# Apex4ROBOTS_UI_1_0.net
KiCad netlist of a schematic drawn in EAGLE
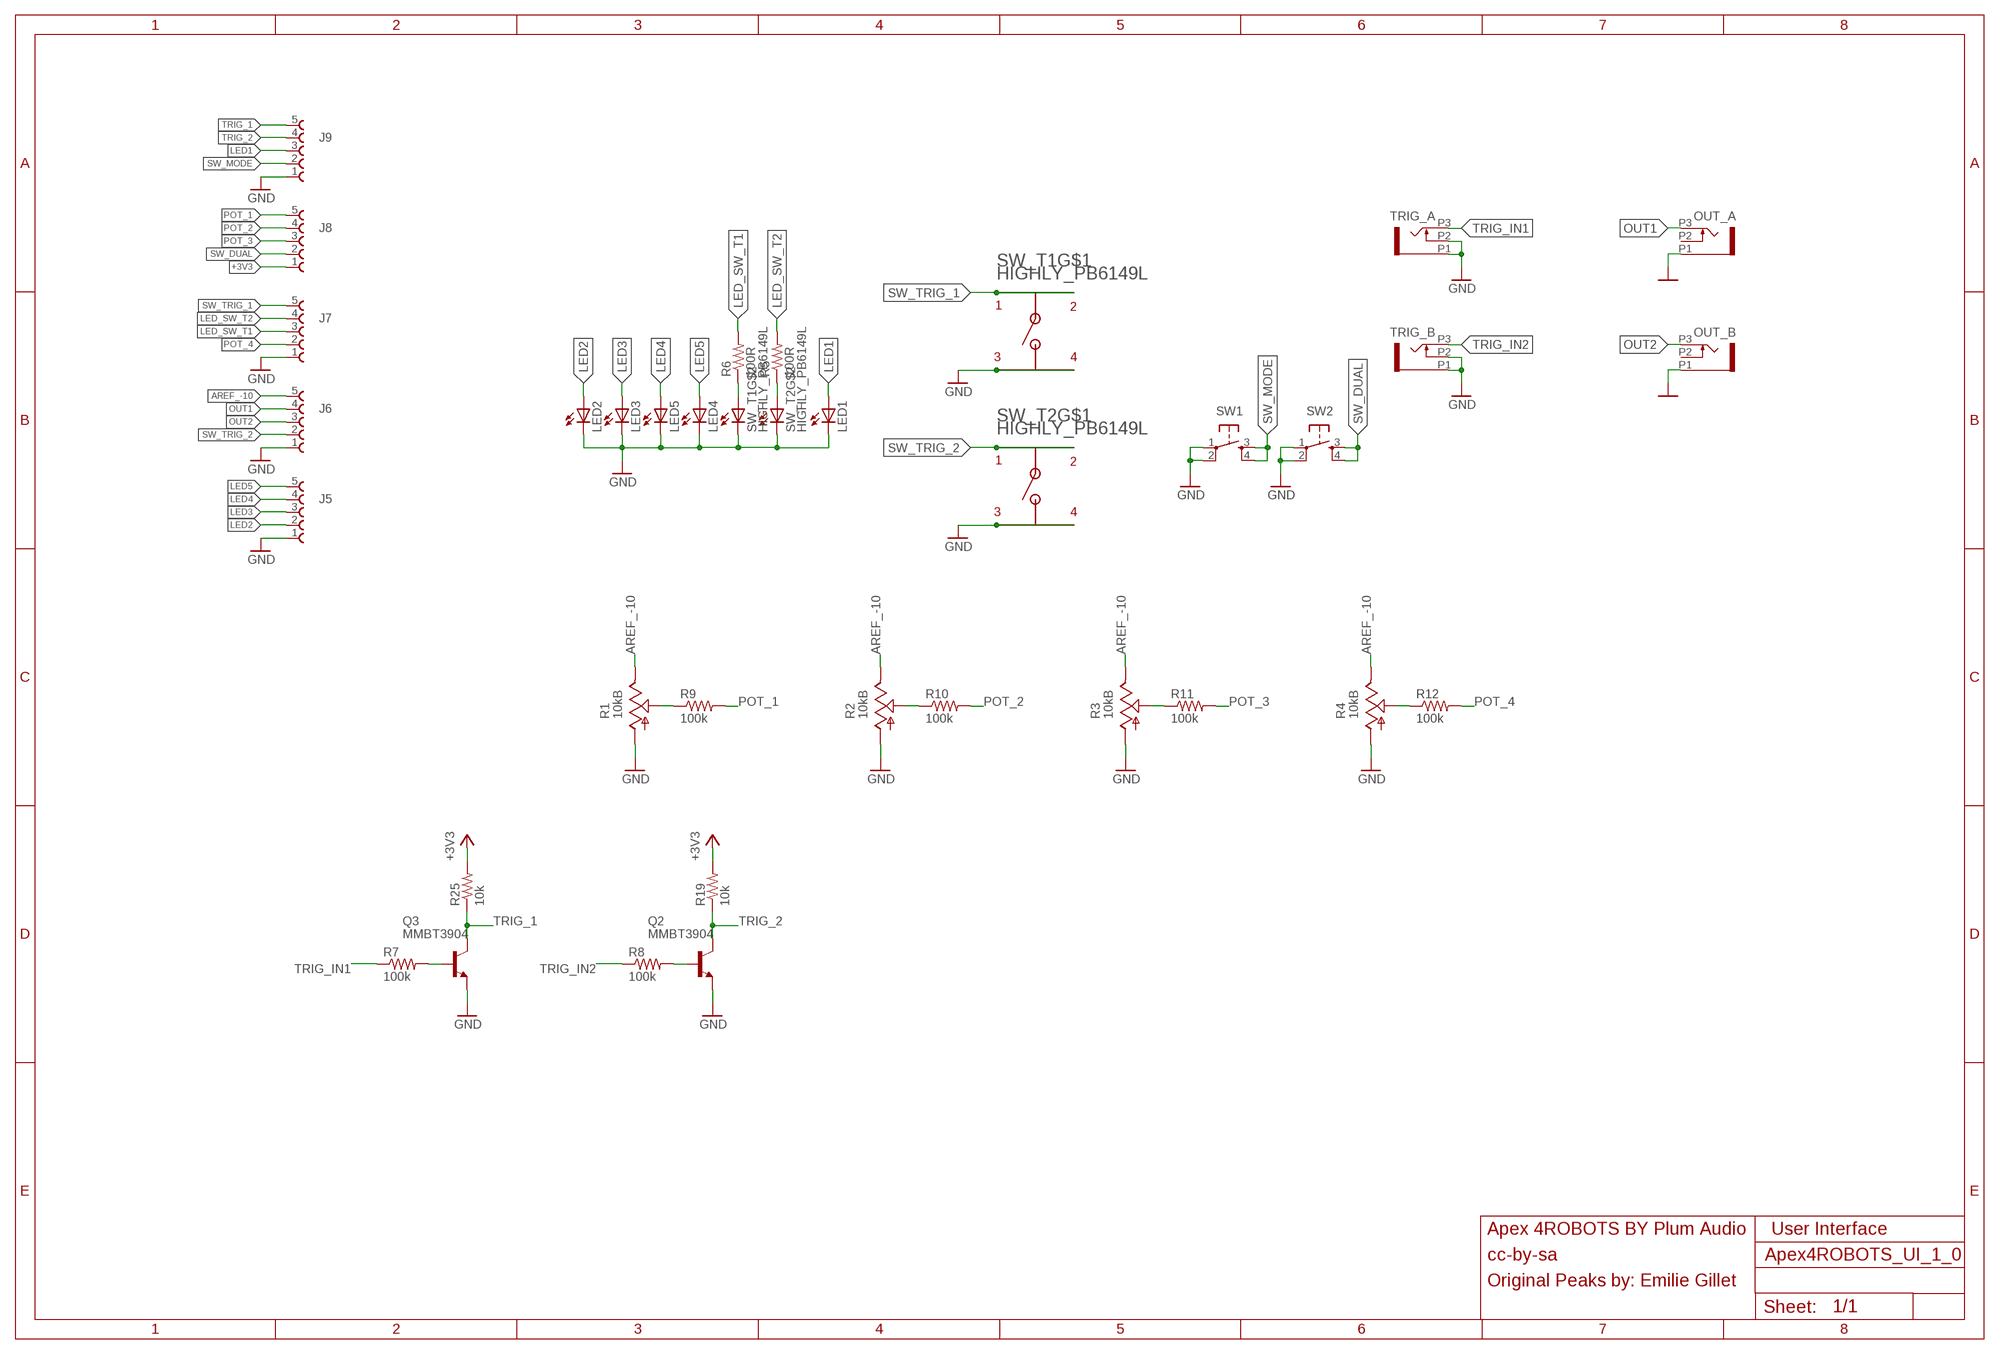
[diagram p0: schematic, sheet 1]

(export (version "E")
  (design (tool "Eeschema 10.0.6"))
  (components
    (comp (ref "J5")
      (value "61300511121")
      (footprint "eagle-import:61300511121")
      (libsource (lib "eagle-import") (part "61300511121"))
    )
    (comp (ref "J6")
      (value "61300511121")
      (footprint "eagle-import:61300511121")
      (libsource (lib "eagle-import") (part "61300511121"))
    )
    (comp (ref "J7")
      (value "61300511121")
      (footprint "eagle-import:61300511121")
      (libsource (lib "eagle-import") (part "61300511121"))
    )
    (comp (ref "J8")
      (value "61300511121")
      (footprint "eagle-import:61300511121")
      (libsource (lib "eagle-import") (part "61300511121"))
    )
    (comp (ref "J9")
      (value "61300511121")
      (footprint "eagle-import:61300511121")
      (libsource (lib "eagle-import") (part "61300511121"))
    )
    (comp (ref "LED1")
      (value "LED3MM")
      (footprint "eagle-import:LED3MM")
      (libsource (lib "eagle-import") (part "LED3MM"))
    )
    (comp (ref "LED2")
      (value "LED3MM")
      (footprint "eagle-import:LED3MM")
      (libsource (lib "eagle-import") (part "LED3MM"))
    )
    (comp (ref "LED3")
      (value "LED3MM")
      (footprint "eagle-import:LED3MM")
      (libsource (lib "eagle-import") (part "LED3MM"))
    )
    (comp (ref "LED4")
      (value "LED3MM")
      (footprint "eagle-import:LED3MM")
      (libsource (lib "eagle-import") (part "LED3MM"))
    )
    (comp (ref "LED5")
      (value "LED3MM")
      (footprint "eagle-import:LED3MM")
      (libsource (lib "eagle-import") (part "LED3MM"))
    )
    (comp (ref "OUT_A")
      (value "OG-PJ301_PJ301_THONKICONN6")
      (footprint "eagle-import:OG-PJ301_WQP_PJ_301M6")
      (libsource (lib "eagle-import") (part "OG-PJ301_PJ301_THONKICONN6"))
    )
    (comp (ref "OUT_B")
      (value "OG-PJ301_PJ301_THONKICONN6")
      (footprint "eagle-import:OG-PJ301_WQP_PJ_301M6")
      (libsource (lib "eagle-import") (part "OG-PJ301_PJ301_THONKICONN6"))
    )
    (comp (ref "Q2")
      (value "MMBT3904")
      (footprint "eagle-import:SOT23-BEC")
      (libsource (lib "eagle-import") (part "-NPN-SOT23-BECMMBT3904LT1"))
    )
    (comp (ref "Q3")
      (value "MMBT3904")
      (footprint "eagle-import:SOT23-BEC")
      (libsource (lib "eagle-import") (part "-NPN-SOT23-BECMMBT3904LT1"))
    )
    (comp (ref "R1")
      (value "10kB")
      (footprint "eagle-import:POTS_TALL_TRIMMER_POT_VERTICAL_SLOTED")
      (libsource (lib "eagle-import") (part "POTS_POT_USSLOTED_TALL_TRIMMER"))
    )
    (comp (ref "R2")
      (value "10kB")
      (footprint "eagle-import:POTS_TALL_TRIMMER_POT_VERTICAL_SLOTED")
      (libsource (lib "eagle-import") (part "POTS_POT_USSLOTED_TALL_TRIMMER"))
    )
    (comp (ref "R3")
      (value "10kB")
      (footprint "eagle-import:POTS_TALL_TRIMMER_POT_VERTICAL_SLOTED")
      (libsource (lib "eagle-import") (part "POTS_POT_USSLOTED_TALL_TRIMMER"))
    )
    (comp (ref "R4")
      (value "10kB")
      (footprint "eagle-import:POTS_TALL_TRIMMER_POT_VERTICAL_SLOTED")
      (libsource (lib "eagle-import") (part "POTS_POT_USSLOTED_TALL_TRIMMER"))
    )
    (comp (ref "R5")
      (value "100R")
      (footprint "eagle-import:R0603")
      (libsource (lib "eagle-import") (part "R-US_R0603"))
    )
    (comp (ref "R6")
      (value "100R")
      (footprint "eagle-import:R0603")
      (libsource (lib "eagle-import") (part "R-US_R0603"))
    )
    (comp (ref "R7")
      (value "100k")
      (footprint "eagle-import:R0603")
      (libsource (lib "eagle-import") (part "R-US_R0603"))
    )
    (comp (ref "R8")
      (value "100k")
      (footprint "eagle-import:R0603")
      (libsource (lib "eagle-import") (part "R-US_R0603"))
    )
    (comp (ref "R9")
      (value "100k")
      (footprint "eagle-import:R0603")
      (libsource (lib "eagle-import") (part "R-US_R0603"))
    )
    (comp (ref "R10")
      (value "100k")
      (footprint "eagle-import:R0603")
      (libsource (lib "eagle-import") (part "R-US_R0603"))
    )
    (comp (ref "R11")
      (value "100k")
      (footprint "eagle-import:R0603")
      (libsource (lib "eagle-import") (part "R-US_R0603"))
    )
    (comp (ref "R12")
      (value "100k")
      (footprint "eagle-import:R0603")
      (libsource (lib "eagle-import") (part "R-US_R0603"))
    )
    (comp (ref "R19")
      (value "10k")
      (footprint "eagle-import:R0603")
      (libsource (lib "eagle-import") (part "R-US_R0603"))
    )
    (comp (ref "R25")
      (value "10k")
      (footprint "eagle-import:R0603")
      (libsource (lib "eagle-import") (part "R-US_R0603"))
    )
    (comp (ref "SW1")
      (value "TAC_SWITCHPTH")
      (footprint "eagle-import:TACTILE-PTH")
      (libsource (lib "eagle-import") (part "TAC_SWITCHPTH"))
    )
    (comp (ref "SW2")
      (value "TAC_SWITCHPTH")
      (footprint "eagle-import:TACTILE-PTH")
      (libsource (lib "eagle-import") (part "TAC_SWITCHPTH"))
    )
    (comp (ref "SW_T1")
      (value "HIGHLY_PB6149L")
      (footprint "eagle-import:HIGHLY_PB64149L")
      (fields (field (name "SPICEPREFIX") "S"))
      (libsource (lib "eagle-import") (part "HIGHLY_PB6149L"))
    )
    (comp (ref "SW_T2")
      (value "HIGHLY_PB6149L")
      (footprint "eagle-import:HIGHLY_PB64149L")
      (libsource (lib "eagle-import") (part "HIGHLY_PB6149L"))
    )
    (comp (ref "TRIG_A")
      (value "OG-PJ301_PJ301_THONKICONN6")
      (footprint "eagle-import:OG-PJ301_WQP_PJ_301M6")
      (libsource (lib "eagle-import") (part "OG-PJ301_PJ301_THONKICONN6"))
    )
    (comp (ref "TRIG_B")
      (value "OG-PJ301_PJ301_THONKICONN6")
      (footprint "eagle-import:OG-PJ301_WQP_PJ_301M6")
      (libsource (lib "eagle-import") (part "OG-PJ301_PJ301_THONKICONN6"))
    )
  )
  (nets
    (net (code "1") (name "+3V3") (class "Default")
      (node (ref "J8") (pin "1") (pinfunction "5_1") (pintype "passive"))
      (node (ref "R19") (pin "2") (pinfunction "2_2") (pintype "passive"))
      (node (ref "R25") (pin "2") (pinfunction "2_2") (pintype "passive"))
    )
    (net (code "2") (name "AREF_-10") (class "Default")
      (node (ref "J6") (pin "5") (pinfunction "1_5") (pintype "passive"))
      (node (ref "R1") (pin "P$1") (pinfunction "E_P$1") (pintype "passive"))
      (node (ref "R2") (pin "P$1") (pinfunction "E_P$1") (pintype "passive"))
      (node (ref "R3") (pin "P$1") (pinfunction "E_P$1") (pintype "passive"))
      (node (ref "R4") (pin "P$1") (pinfunction "E_P$1") (pintype "passive"))
    )
    (net (code "3") (name "GND") (class "Default")
      (node (ref "J5") (pin "1") (pinfunction "5_1") (pintype "passive"))
      (node (ref "J6") (pin "1") (pinfunction "5_1") (pintype "passive"))
      (node (ref "J7") (pin "1") (pinfunction "5_1") (pintype "passive"))
      (node (ref "J9") (pin "1") (pinfunction "5_1") (pintype "passive"))
      (node (ref "LED1") (pin "K") (pinfunction "C_K") (pintype "passive"))
      (node (ref "LED2") (pin "K") (pinfunction "C_K") (pintype "passive"))
      (node (ref "LED3") (pin "K") (pinfunction "C_K") (pintype "passive"))
      (node (ref "LED4") (pin "K") (pinfunction "C_K") (pintype "passive"))
      (node (ref "LED5") (pin "K") (pinfunction "C_K") (pintype "passive"))
      (node (ref "OUT_A") (pin "P1") (pinfunction "1_P1") (pintype "passive"))
      (node (ref "OUT_B") (pin "P1") (pinfunction "1_P1") (pintype "passive"))
      (node (ref "Q2") (pin "E") (pinfunction "E_E") (pintype "passive"))
      (node (ref "Q3") (pin "E") (pinfunction "E_E") (pintype "passive"))
      (node (ref "R1") (pin "P$3") (pinfunction "A_P$3") (pintype "passive"))
      (node (ref "R2") (pin "P$3") (pinfunction "A_P$3") (pintype "passive"))
      (node (ref "R3") (pin "P$3") (pinfunction "A_P$3") (pintype "passive"))
      (node (ref "R4") (pin "P$3") (pinfunction "A_P$3") (pintype "passive"))
      (node (ref "SW1") (pin "1") (pinfunction "1_1") (pintype "passive"))
      (node (ref "SW1") (pin "2") (pinfunction "2_2") (pintype "passive"))
      (node (ref "SW2") (pin "1") (pinfunction "1_1") (pintype "passive"))
      (node (ref "SW2") (pin "2") (pinfunction "2_2") (pintype "passive"))
      (node (ref "SW_T1") (pin "L2") (pinfunction "L2_L2") (pintype "passive"))
      (node (ref "SW_T1") (pin "P$3") (pinfunction "P$3_P$3") (pintype "bidirectional"))
      (node (ref "SW_T1") (pin "P$4") (pinfunction "P$4_P$4") (pintype "bidirectional"))
      (node (ref "SW_T2") (pin "L2") (pinfunction "L2_L2") (pintype "passive"))
      (node (ref "SW_T2") (pin "P$3") (pinfunction "P$3_P$3") (pintype "bidirectional"))
      (node (ref "SW_T2") (pin "P$4") (pinfunction "P$4_P$4") (pintype "bidirectional"))
      (node (ref "TRIG_A") (pin "P1") (pinfunction "1_P1") (pintype "passive"))
      (node (ref "TRIG_A") (pin "P2") (pinfunction "2_P2") (pintype "passive"))
      (node (ref "TRIG_B") (pin "P1") (pinfunction "1_P1") (pintype "passive"))
      (node (ref "TRIG_B") (pin "P2") (pinfunction "2_P2") (pintype "passive"))
    )
    (net (code "4") (name "LED1") (class "Default")
      (node (ref "J9") (pin "3") (pinfunction "3_3") (pintype "passive"))
      (node (ref "LED1") (pin "A") (pinfunction "A_A") (pintype "passive"))
    )
    (net (code "5") (name "LED2") (class "Default")
      (node (ref "J5") (pin "2") (pinfunction "4_2") (pintype "passive"))
      (node (ref "LED2") (pin "A") (pinfunction "A_A") (pintype "passive"))
    )
    (net (code "6") (name "LED3") (class "Default")
      (node (ref "J5") (pin "3") (pinfunction "3_3") (pintype "passive"))
      (node (ref "LED3") (pin "A") (pinfunction "A_A") (pintype "passive"))
    )
    (net (code "7") (name "LED4") (class "Default")
      (node (ref "J5") (pin "4") (pinfunction "2_4") (pintype "passive"))
      (node (ref "LED5") (pin "A") (pinfunction "A_A") (pintype "passive"))
    )
    (net (code "8") (name "LED5") (class "Default")
      (node (ref "J5") (pin "5") (pinfunction "1_5") (pintype "passive"))
      (node (ref "LED4") (pin "A") (pinfunction "A_A") (pintype "passive"))
    )
    (net (code "9") (name "LED_SW_T1") (class "Default")
      (node (ref "J7") (pin "3") (pinfunction "3_3") (pintype "passive"))
      (node (ref "R6") (pin "2") (pinfunction "2_2") (pintype "passive"))
    )
    (net (code "10") (name "LED_SW_T2") (class "Default")
      (node (ref "J7") (pin "4") (pinfunction "2_4") (pintype "passive"))
      (node (ref "R5") (pin "2") (pinfunction "2_2") (pintype "passive"))
    )
    (net (code "11") (name "Net-(Q2-PadB)") (class "Default")
      (node (ref "Q2") (pin "B") (pinfunction "B_B") (pintype "passive"))
      (node (ref "R8") (pin "2") (pinfunction "2_2") (pintype "passive"))
    )
    (net (code "12") (name "Net-(Q3-PadB)") (class "Default")
      (node (ref "Q3") (pin "B") (pinfunction "B_B") (pintype "passive"))
      (node (ref "R7") (pin "2") (pinfunction "2_2") (pintype "passive"))
    )
    (net (code "13") (name "Net-(R1-S)") (class "Default")
      (node (ref "R1") (pin "P$2") (pinfunction "S_P$2") (pintype "passive"))
      (node (ref "R9") (pin "1") (pinfunction "1_1") (pintype "passive"))
    )
    (net (code "14") (name "Net-(R2-S)") (class "Default")
      (node (ref "R10") (pin "1") (pinfunction "1_1") (pintype "passive"))
      (node (ref "R2") (pin "P$2") (pinfunction "S_P$2") (pintype "passive"))
    )
    (net (code "15") (name "Net-(R3-S)") (class "Default")
      (node (ref "R11") (pin "1") (pinfunction "1_1") (pintype "passive"))
      (node (ref "R3") (pin "P$2") (pinfunction "S_P$2") (pintype "passive"))
    )
    (net (code "16") (name "Net-(R4-S)") (class "Default")
      (node (ref "R12") (pin "1") (pinfunction "1_1") (pintype "passive"))
      (node (ref "R4") (pin "P$2") (pinfunction "S_P$2") (pintype "passive"))
    )
    (net (code "17") (name "Net-(R5-Pad1)") (class "Default")
      (node (ref "R5") (pin "1") (pinfunction "1_1") (pintype "passive"))
      (node (ref "SW_T2") (pin "L1") (pinfunction "L1_L1") (pintype "passive"))
    )
    (net (code "18") (name "Net-(R6-Pad1)") (class "Default")
      (node (ref "R6") (pin "1") (pinfunction "1_1") (pintype "passive"))
      (node (ref "SW_T1") (pin "L1") (pinfunction "L1_L1") (pintype "passive"))
    )
    (net (code "19") (name "OUT1") (class "Default")
      (node (ref "J6") (pin "4") (pinfunction "2_4") (pintype "passive"))
      (node (ref "OUT_A") (pin "P3") (pinfunction "3_P3") (pintype "passive"))
    )
    (net (code "20") (name "OUT2") (class "Default")
      (node (ref "J6") (pin "3") (pinfunction "3_3") (pintype "passive"))
      (node (ref "OUT_B") (pin "P3") (pinfunction "3_P3") (pintype "passive"))
    )
    (net (code "21") (name "POT_1") (class "Default")
      (node (ref "J8") (pin "5") (pinfunction "1_5") (pintype "passive"))
      (node (ref "R9") (pin "2") (pinfunction "2_2") (pintype "passive"))
    )
    (net (code "22") (name "POT_2") (class "Default")
      (node (ref "J8") (pin "4") (pinfunction "2_4") (pintype "passive"))
      (node (ref "R10") (pin "2") (pinfunction "2_2") (pintype "passive"))
    )
    (net (code "23") (name "POT_3") (class "Default")
      (node (ref "J8") (pin "3") (pinfunction "3_3") (pintype "passive"))
      (node (ref "R11") (pin "2") (pinfunction "2_2") (pintype "passive"))
    )
    (net (code "24") (name "POT_4") (class "Default")
      (node (ref "J7") (pin "2") (pinfunction "4_2") (pintype "passive"))
      (node (ref "R12") (pin "2") (pinfunction "2_2") (pintype "passive"))
    )
    (net (code "25") (name "SW_DUAL") (class "Default")
      (node (ref "J8") (pin "2") (pinfunction "4_2") (pintype "passive"))
      (node (ref "SW2") (pin "3") (pinfunction "3_3") (pintype "passive"))
      (node (ref "SW2") (pin "4") (pinfunction "4_4") (pintype "passive"))
    )
    (net (code "26") (name "SW_MODE") (class "Default")
      (node (ref "J9") (pin "2") (pinfunction "4_2") (pintype "passive"))
      (node (ref "SW1") (pin "3") (pinfunction "3_3") (pintype "passive"))
      (node (ref "SW1") (pin "4") (pinfunction "4_4") (pintype "passive"))
    )
    (net (code "27") (name "SW_TRIG_1") (class "Default")
      (node (ref "J7") (pin "5") (pinfunction "1_5") (pintype "passive"))
      (node (ref "SW_T1") (pin "P$1") (pinfunction "P$1_P$1") (pintype "bidirectional"))
      (node (ref "SW_T1") (pin "P$2") (pinfunction "P$2_P$2") (pintype "bidirectional"))
    )
    (net (code "28") (name "SW_TRIG_2") (class "Default")
      (node (ref "J6") (pin "2") (pinfunction "4_2") (pintype "passive"))
      (node (ref "SW_T2") (pin "P$1") (pinfunction "P$1_P$1") (pintype "bidirectional"))
      (node (ref "SW_T2") (pin "P$2") (pinfunction "P$2_P$2") (pintype "bidirectional"))
    )
    (net (code "29") (name "TRIG_1") (class "Default")
      (node (ref "J9") (pin "5") (pinfunction "1_5") (pintype "passive"))
      (node (ref "Q3") (pin "C") (pinfunction "C_C") (pintype "passive"))
      (node (ref "R25") (pin "1") (pinfunction "1_1") (pintype "passive"))
    )
    (net (code "30") (name "TRIG_2") (class "Default")
      (node (ref "J9") (pin "4") (pinfunction "2_4") (pintype "passive"))
      (node (ref "Q2") (pin "C") (pinfunction "C_C") (pintype "passive"))
      (node (ref "R19") (pin "1") (pinfunction "1_1") (pintype "passive"))
    )
    (net (code "31") (name "TRIG_IN1") (class "Default")
      (node (ref "R7") (pin "1") (pinfunction "1_1") (pintype "passive"))
      (node (ref "TRIG_A") (pin "P3") (pinfunction "3_P3") (pintype "passive"))
    )
    (net (code "32") (name "TRIG_IN2") (class "Default")
      (node (ref "R8") (pin "1") (pinfunction "1_1") (pintype "passive"))
      (node (ref "TRIG_B") (pin "P3") (pinfunction "3_P3") (pintype "passive"))
    )
    (net (code "33") (name "unconnected-(OUT_A-2-PadP2)") (class "Default")
      (node (ref "OUT_A") (pin "P2") (pinfunction "2_P2") (pintype "passive"))
    )
    (net (code "34") (name "unconnected-(OUT_B-2-PadP2)") (class "Default")
      (node (ref "OUT_B") (pin "P2") (pinfunction "2_P2") (pintype "passive"))
    )
  )
)
